# UWB-IP-Hardware.net
KiCad netlist of a schematic drawn in Altium Designer
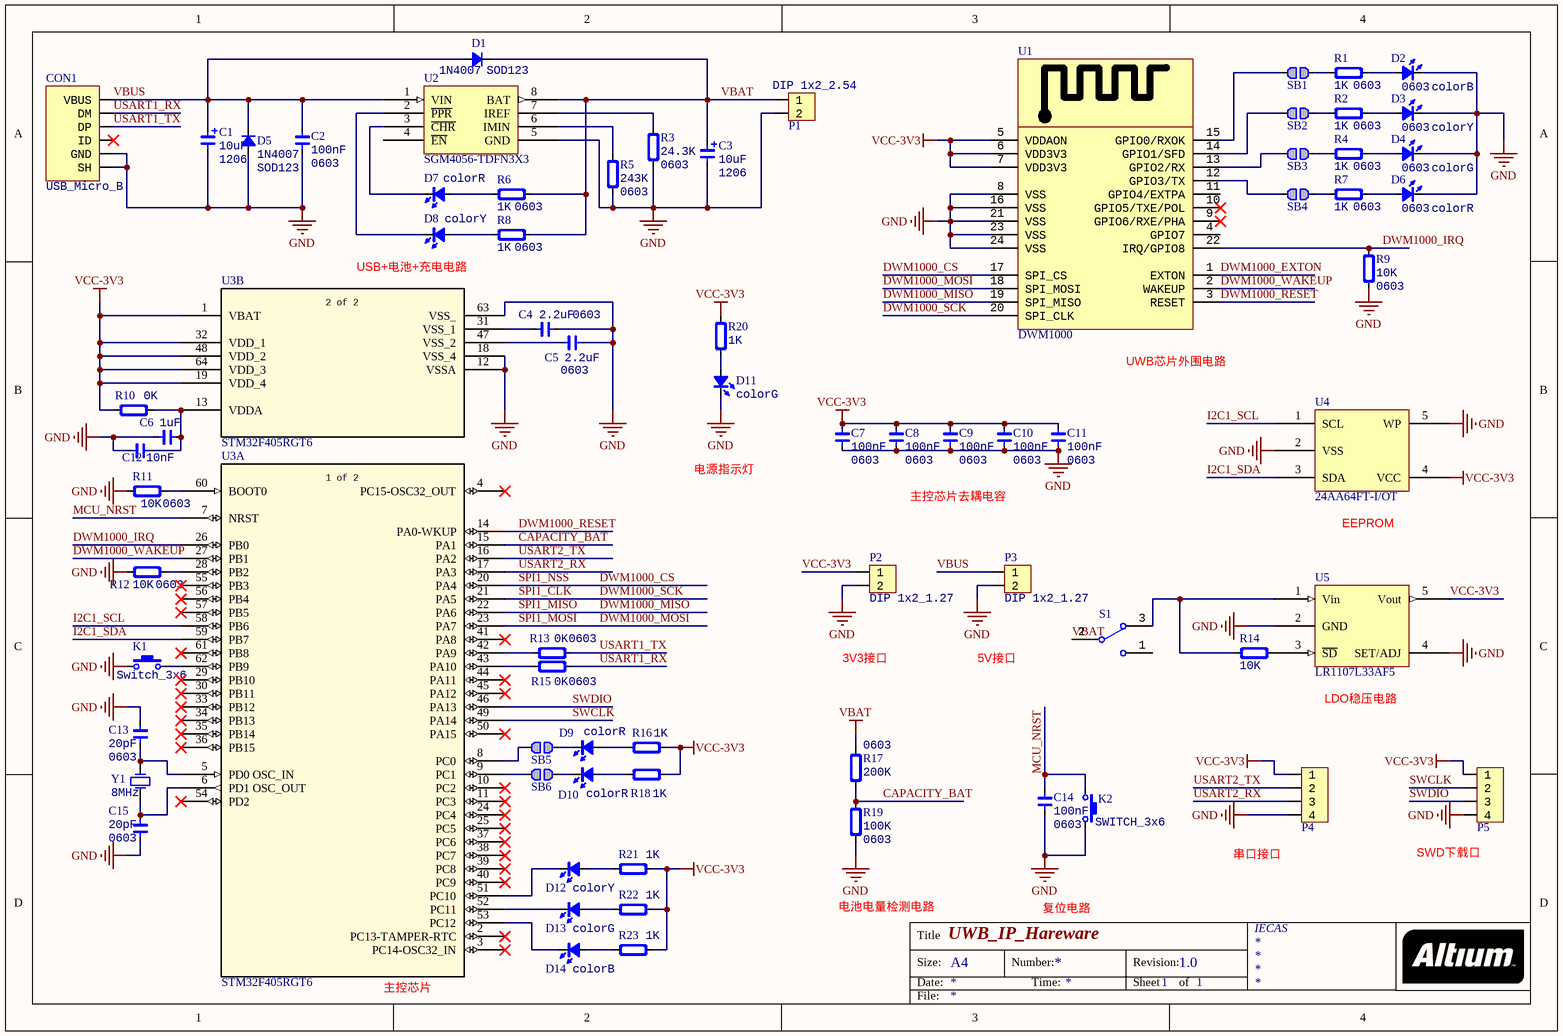
[diagram p0: UWB-IP-Hardware.SchDoc]

(export (version "E")
  (design (tool "Eeschema 10.0.6"))
  (components
    (comp (ref "C1")
      (value "10uF")
      (footprint "PCB_PassiveCap:CAP_TAN_A1206")
      (description "Capacitor Tantalum")
      (fields (field (name "TYPE") "1206"))
      (libsource (lib "SCH_Passive") (part "Cap_Tan_1206"))
    )
    (comp (ref "C2")
      (value "100nF")
      (footprint "PCB_PassiveCap:CAP_0603")
      (description "Capacitor")
      (fields (field (name "TYPE") "0603"))
      (libsource (lib "SCH_Passive") (part "Cap_0603"))
    )
    (comp (ref "C3")
      (value "10uF")
      (footprint "PCB_PassiveCap:CAP_TAN_A1206")
      (description "Capacitor Tantalum")
      (fields (field (name "TYPE") "1206"))
      (libsource (lib "SCH_Passive") (part "Cap_Tan_1206"))
    )
    (comp (ref "C4")
      (value "2.2uF")
      (footprint "PCB_PassiveCap:CAP_0603")
      (description "Capacitor")
      (fields (field (name "TYPE") "0603"))
      (libsource (lib "") (part "Cap_0603_1"))
    )
    (comp (ref "C5")
      (value "2.2uF")
      (footprint "PCB_PassiveCap:CAP_0603")
      (description "Capacitor")
      (fields (field (name "TYPE") "0603"))
      (libsource (lib "") (part "Cap_0603_1"))
    )
    (comp (ref "C6")
      (value "1uF")
      (footprint "PCB_PassiveCap:CAP_0603")
      (description "Capacitor")
      (libsource (lib "") (part "Cap_0603_2"))
    )
    (comp (ref "C7")
      (value "100nF")
      (footprint "PCB_PassiveCap:CAP_0603")
      (description "Capacitor")
      (fields (field (name "TYPE") "0603"))
      (libsource (lib "SCH_Passive") (part "Cap_0603"))
    )
    (comp (ref "C8")
      (value "100nF")
      (footprint "PCB_PassiveCap:CAP_0603")
      (description "Capacitor")
      (fields (field (name "TYPE") "0603"))
      (libsource (lib "SCH_Passive") (part "Cap_0603"))
    )
    (comp (ref "C9")
      (value "100nF")
      (footprint "PCB_PassiveCap:CAP_0603")
      (description "Capacitor")
      (fields (field (name "TYPE") "0603"))
      (libsource (lib "SCH_Passive") (part "Cap_0603"))
    )
    (comp (ref "C10")
      (value "100nF")
      (footprint "PCB_PassiveCap:CAP_0603")
      (description "Capacitor")
      (fields (field (name "TYPE") "0603"))
      (libsource (lib "SCH_Passive") (part "Cap_0603"))
    )
    (comp (ref "C11")
      (value "100nF")
      (footprint "PCB_PassiveCap:CAP_0603")
      (description "Capacitor")
      (fields (field (name "TYPE") "0603"))
      (libsource (lib "SCH_Passive") (part "Cap_0603"))
    )
    (comp (ref "C12")
      (value "10nF")
      (footprint "PCB_PassiveCap:CAP_0603")
      (description "Capacitor")
      (libsource (lib "") (part "Cap_0603_2"))
    )
    (comp (ref "C13")
      (value "20pF")
      (footprint "PCB_PassiveCap:CAP_0603")
      (description "Capacitor")
      (fields (field (name "TYPE") "0603"))
      (libsource (lib "SCH_Passive") (part "Cap_0603"))
    )
    (comp (ref "C14")
      (value "100nF")
      (footprint "PCB_PassiveCap:CAP_0603")
      (description "Capacitor")
      (fields (field (name "TYPE") "0603"))
      (libsource (lib "SCH_Passive") (part "Cap_0603"))
    )
    (comp (ref "C15")
      (value "20pF")
      (footprint "PCB_PassiveCap:CAP_0603")
      (description "Capacitor")
      (fields (field (name "TYPE") "0603"))
      (libsource (lib "SCH_Passive") (part "Cap_0603"))
    )
    (comp (ref "CON1")
      (value "USB_Micro_B")
      (footprint "PCB_USB:USB_Micro-AB")
      (description "USB")
      (libsource (lib "SCH_USB") (part "USB_Micro"))
    )
    (comp (ref "D1")
      (value "1N4007")
      (footprint "PCB_ActiveDIO:SOD-123")
      (description "Diode")
      (fields (field (name "TYPE") "SOD123"))
      (libsource (lib "SCH_Active") (part "Diode_SOD123"))
    )
    (comp (ref "D2")
      (value "colorB")
      (footprint "PCB_ActiveLED:LED_0603_BLUE")
      (description "LED")
      (fields (field (name "TYPE") "0603"))
      (libsource (lib "") (part "LED_0603_1"))
    )
    (comp (ref "D3")
      (value "colorY")
      (footprint "PCB_ActiveLED:LED_0603_YELLOW")
      (description "LED")
      (fields (field (name "TYPE") "0603"))
      (libsource (lib "") (part "LED_0603_1"))
    )
    (comp (ref "D4")
      (value "colorG")
      (footprint "PCB_ActiveLED:LED_0603_GREEN")
      (description "LED")
      (fields (field (name "TYPE") "0603"))
      (libsource (lib "") (part "LED_0603_1"))
    )
    (comp (ref "D5")
      (value "1N4007")
      (footprint "PCB_ActiveDIO:SOD-123")
      (description "Diode")
      (fields (field (name "TYPE") "SOD123"))
      (libsource (lib "SCH_Active") (part "Diode_SOD123"))
    )
    (comp (ref "D6")
      (value "colorR")
      (footprint "PCB_ActiveLED:LED_0603_RED")
      (description "LED")
      (fields (field (name "TYPE") "0603"))
      (libsource (lib "") (part "LED_0603_1"))
    )
    (comp (ref "D7")
      (value "colorR")
      (footprint "PCB_ActiveLED:LED_0603_RED")
      (description "LED")
      (libsource (lib "SCH_Active") (part "LED_0603"))
    )
    (comp (ref "D8")
      (value "colorY")
      (footprint "PCB_ActiveLED:LED_0603_YELLOW")
      (description "LED")
      (libsource (lib "SCH_Active") (part "LED_0603"))
    )
    (comp (ref "D9")
      (value "colorR")
      (footprint "PCB_ActiveLED:LED_0603_RED")
      (description "LED")
      (libsource (lib "SCH_Active") (part "LED_0603"))
    )
    (comp (ref "D10")
      (value "colorR")
      (footprint "PCB_ActiveLED:LED_0603_BLUE")
      (description "LED")
      (libsource (lib "SCH_Active") (part "LED_0603"))
    )
    (comp (ref "D11")
      (value "colorG")
      (footprint "PCB_ActiveLED:LED_0603_GREEN")
      (description "LED")
      (libsource (lib "") (part "LED_0603_2"))
    )
    (comp (ref "D12")
      (value "colorY")
      (footprint "PCB_ActiveLED:LED_0603_YELLOW")
      (description "LED")
      (libsource (lib "SCH_Active") (part "LED_0603"))
    )
    (comp (ref "D13")
      (value "colorG")
      (footprint "PCB_ActiveLED:LED_0603_GREEN")
      (description "LED")
      (libsource (lib "SCH_Active") (part "LED_0603"))
    )
    (comp (ref "D14")
      (value "colorB")
      (footprint "PCB_ActiveLED:LED_0603_BLUE")
      (description "LED")
      (libsource (lib "SCH_Active") (part "LED_0603"))
    )
    (comp (ref "K1")
      (value "Switch_3x6")
      (footprint "PCB_Switch:ButtonTACT_3x6x2.5_180")
      (description "Button")
      (libsource (lib "SCH_Switch") (part "ButtonTACT_3x6x2.5_180"))
    )
    (comp (ref "K2")
      (value "SWITCH_3x6")
      (footprint "PCB_Switch:ButtonTACT_3x6x2.5_180")
      (description "Button")
      (libsource (lib "SCH_Switch") (part "ButtonTACT_3x6x2.5_180"))
    )
    (comp (ref "P1")
      (value "DIP 1x2_2.54")
      (footprint "PCB_ConnectorHDR:HDR1X2_2.54_180")
      (description "Header")
      (libsource (lib "SCH_ConnectorHDR") (part "HDR1x2_2.54"))
    )
    (comp (ref "P2")
      (value "DIP 1x2_1.27")
      (footprint "PCB_ConnectorHDR:HDR1X2_1.27_180")
      (description "Header")
      (libsource (lib "SCH_ConnectorHDR") (part "HDR1x2_1.27"))
    )
    (comp (ref "P3")
      (value "DIP 1x2_1.27")
      (footprint "PCB_ConnectorHDR:HDR1X2_1.27_180")
      (description "Header")
      (libsource (lib "SCH_ConnectorHDR") (part "HDR1x2_1.27"))
    )
    (comp (ref "P4")
      (value "HDR1x4_2.54")
      (footprint "PCB_ConnectorHDR:HDR1x4_2.54_180")
      (description "Header")
      (libsource (lib "SCH_ConnectorHDR") (part "HDR1x4_2.54"))
    )
    (comp (ref "P5")
      (value "HDR1x4_2.54")
      (footprint "PCB_ConnectorHDR:HDR1x4_2.54_180")
      (description "Header")
      (libsource (lib "SCH_ConnectorHDR") (part "HDR1x4_2.54"))
    )
    (comp (ref "R1")
      (value "1K")
      (footprint "PCB_PassiveRes:RES_0603")
      (description "Resistor")
      (fields (field (name "TYPE") "0603"))
      (libsource (lib "SCH_Passive") (part "Res_0603"))
    )
    (comp (ref "R2")
      (value "1K")
      (footprint "PCB_PassiveRes:RES_0603")
      (description "Resistor")
      (fields (field (name "TYPE") "0603"))
      (libsource (lib "SCH_Passive") (part "Res_0603"))
    )
    (comp (ref "R3")
      (value "24.3K")
      (footprint "PCB_PassiveRes:RES_0603")
      (description "Resistor")
      (fields (field (name "TYPE") "0603"))
      (libsource (lib "SCH_Passive") (part "Res_0603"))
    )
    (comp (ref "R4")
      (value "1K")
      (footprint "PCB_PassiveRes:RES_0603")
      (description "Resistor")
      (fields (field (name "TYPE") "0603"))
      (libsource (lib "SCH_Passive") (part "Res_0603"))
    )
    (comp (ref "R5")
      (value "243K")
      (footprint "PCB_PassiveRes:RES_0603")
      (description "Resistor")
      (fields (field (name "TYPE") "0603"))
      (libsource (lib "SCH_Passive") (part "Res_0603"))
    )
    (comp (ref "R6")
      (value "1K")
      (footprint "PCB_PassiveRes:RES_0603")
      (description "Resistor")
      (fields (field (name "TYPE") "0603"))
      (libsource (lib "SCH_Passive") (part "Res_0603"))
    )
    (comp (ref "R7")
      (value "1K")
      (footprint "PCB_PassiveRes:RES_0603")
      (description "Resistor")
      (fields (field (name "TYPE") "0603"))
      (libsource (lib "SCH_Passive") (part "Res_0603"))
    )
    (comp (ref "R8")
      (value "1K")
      (footprint "PCB_PassiveRes:RES_0603")
      (description "Resistor")
      (fields (field (name "TYPE") "0603"))
      (libsource (lib "SCH_Passive") (part "Res_0603"))
    )
    (comp (ref "R9")
      (value "10K")
      (footprint "PCB_PassiveRes:RES_0603")
      (description "Resistor")
      (fields (field (name "TYPE") "0603"))
      (libsource (lib "SCH_Passive") (part "Res_0603"))
    )
    (comp (ref "R10")
      (value "0K")
      (footprint "PCB_PassiveRes:RES_0603")
      (description "Resistor")
      (libsource (lib "SCH_Passive") (part "Res_0603"))
    )
    (comp (ref "R11")
      (value "10K")
      (footprint "PCB_PassiveRes:RES_0603")
      (description "Resistor")
      (fields (field (name "TYPE") "0603"))
      (libsource (lib "SCH_Passive") (part "Res_0603"))
    )
    (comp (ref "R12")
      (value "10K")
      (footprint "PCB_PassiveRes:RES_0603")
      (description "Resistor")
      (fields (field (name "TYPE") "0603"))
      (libsource (lib "SCH_Passive") (part "Res_0603"))
    )
    (comp (ref "R13")
      (value "0K")
      (footprint "PCB_PassiveRes:RES_0603")
      (description "Resistor")
      (fields (field (name "TYPE") "0603"))
      (libsource (lib "SCH_Passive") (part "Res_0603"))
    )
    (comp (ref "R14")
      (value "10K")
      (footprint "PCB_PassiveRes:RES_0603")
      (description "Resistor")
      (libsource (lib "SCH_Passive") (part "Res_0603"))
    )
    (comp (ref "R15")
      (value "0K")
      (footprint "PCB_PassiveRes:RES_0603")
      (description "Resistor")
      (fields (field (name "TYPE") "0603"))
      (libsource (lib "SCH_Passive") (part "Res_0603"))
    )
    (comp (ref "R16")
      (value "1K")
      (footprint "PCB_PassiveRes:RES_0603")
      (description "Resistor")
      (libsource (lib "SCH_Passive") (part "Res_0603"))
    )
    (comp (ref "R17")
      (value "200K")
      (footprint "PCB_PassiveRes:RES_0603")
      (description "Resistor")
      (fields (field (name "TYPE") "0603"))
      (libsource (lib "SCH_Passive") (part "Res_0603"))
    )
    (comp (ref "R18")
      (value "1K")
      (footprint "PCB_PassiveRes:RES_0603")
      (description "Resistor")
      (libsource (lib "SCH_Passive") (part "Res_0603"))
    )
    (comp (ref "R19")
      (value "100K")
      (footprint "PCB_PassiveRes:RES_0603")
      (description "Resistor")
      (fields (field (name "TYPE") "0603"))
      (libsource (lib "SCH_Passive") (part "Res_0603"))
    )
    (comp (ref "R20")
      (value "1K")
      (footprint "PCB_PassiveRes:RES_0603")
      (description "Resistor")
      (libsource (lib "SCH_Passive") (part "Res_0603"))
    )
    (comp (ref "R21")
      (value "1K")
      (footprint "PCB_PassiveRes:RES_0603")
      (description "Resistor")
      (libsource (lib "SCH_Passive") (part "Res_0603"))
    )
    (comp (ref "R22")
      (value "1K")
      (footprint "PCB_PassiveRes:RES_0603")
      (description "Resistor")
      (libsource (lib "SCH_Passive") (part "Res_0603"))
    )
    (comp (ref "R23")
      (value "1K")
      (footprint "PCB_PassiveRes:RES_0603")
      (description "Resistor")
      (libsource (lib "SCH_Passive") (part "Res_0603"))
    )
    (comp (ref "S1")
      (value "SPDT 3P")
      (footprint "PCB_Switch:SwitchSPDT_2.8X6.6_90")
      (description "Switch")
      (libsource (lib "SCH_Switch") (part "SwitchSPDT_2.8x6.6_90"))
    )
    (comp (ref "SB1")
      (value "Solderbridge")
      (footprint "PCB_Mechanical:Solderbridge")
      (libsource (lib "SCH_Mechanical") (part "Solderbridge"))
    )
    (comp (ref "SB2")
      (value "Solderbridge")
      (footprint "PCB_Mechanical:Solderbridge")
      (libsource (lib "SCH_Mechanical") (part "Solderbridge"))
    )
    (comp (ref "SB3")
      (value "Solderbridge")
      (footprint "PCB_Mechanical:Solderbridge")
      (libsource (lib "SCH_Mechanical") (part "Solderbridge"))
    )
    (comp (ref "SB4")
      (value "Solderbridge")
      (footprint "PCB_Mechanical:Solderbridge")
      (libsource (lib "SCH_Mechanical") (part "Solderbridge"))
    )
    (comp (ref "SB5")
      (value "Solderbridge")
      (footprint "PCB_Mechanical:Solderbridge")
      (libsource (lib "SCH_Mechanical") (part "Solderbridge"))
    )
    (comp (ref "SB6")
      (value "Solderbridge")
      (footprint "PCB_Mechanical:Solderbridge")
      (libsource (lib "SCH_Mechanical") (part "Solderbridge"))
    )
    (comp (ref "U1")
      (value "DWM1000")
      (footprint "PCB_Module:DWM1000")
      (description "Module")
      (fields (field (name "MANUFACTURER") "Decawave Limited"))
      (libsource (lib "SCH_Module") (part "DWM1000"))
    )
    (comp (ref "U2")
      (value "SGM4056-TDFN3X3")
      (footprint "SGM4056-TDFN3X3-8L")
      (libsource (lib "UWB-IP-Schlib") (part "SGM4056"))
    )
    (comp (ref "U3")
      (value "STM32F405RGT6")
      (footprint "STM32F405RGT6-LQFP-64-M")
      (description "No Description Available")
      (fields (field (name "COPYRIGHT") "Copyright (C) 2018 Accelerated Designs. All rights reserved"))
      (libsource (lib "UWB-IP-Schlib") (part "STM32F405RGT6"))
    )
    (comp (ref "U4")
      (value "24AA64FT-I/OT")
      (footprint "EEPROM_24AA64FT-I/OT")
      (libsource (lib "UWB-IP-Schlib") (part "eeprom_24AA64FT-I/OT"))
    )
    (comp (ref "U5")
      (value "LR1107L33AF5")
      (footprint "LR1107L33AF5")
      (libsource (lib "UWB-IP-Schlib") (part "LR1107/EL33AF5"))
    )
    (comp (ref "Y1")
      (value "8MHz")
      (footprint "PCB_Oscillator:XT_3225_2")
      (description "Crystal Oscillator")
      (libsource (lib "SCH_Oscillator") (part "XTAL_3225_2P"))
    )
  )
  (nets
    (net (code "1") (name "/CAPACITY_BAT") (class "Default")
      (node (ref "R17") (pin "1") (pinfunction "1_1") (pintype "passive"))
      (node (ref "R19") (pin "2") (pinfunction "2_2") (pintype "passive"))
      (node (ref "U3") (pin "15") (pinfunction "PA1_15") (pintype "bidirectional"))
    )
    (net (code "2") (name "/DWM1000_CS") (class "Default")
      (node (ref "U1") (pin "17") (pinfunction "SPI_CS_17") (pintype "passive"))
      (node (ref "U3") (pin "20") (pinfunction "PA4_20") (pintype "bidirectional"))
    )
    (net (code "3") (name "/DWM1000_EXTON") (class "Default")
      (node (ref "U1") (pin "1") (pinfunction "EXTON_1") (pintype "passive"))
    )
    (net (code "4") (name "/DWM1000_IRQ") (class "Default")
      (node (ref "R9") (pin "2") (pinfunction "2_2") (pintype "passive"))
      (node (ref "U1") (pin "22") (pinfunction "IRQ/GPIO8_22") (pintype "passive"))
      (node (ref "U3") (pin "26") (pinfunction "PB0_26") (pintype "bidirectional"))
    )
    (net (code "5") (name "/DWM1000_MISO") (class "Default")
      (node (ref "U1") (pin "19") (pinfunction "SPI_MISO_19") (pintype "passive"))
      (node (ref "U3") (pin "22") (pinfunction "PA6_22") (pintype "bidirectional"))
    )
    (net (code "6") (name "/DWM1000_MOSI") (class "Default")
      (node (ref "U1") (pin "18") (pinfunction "SPI_MOSI_18") (pintype "passive"))
      (node (ref "U3") (pin "23") (pinfunction "PA7_23") (pintype "bidirectional"))
    )
    (net (code "7") (name "/DWM1000_RESET") (class "Default")
      (node (ref "U1") (pin "3") (pinfunction "RESET_3") (pintype "passive"))
      (node (ref "U3") (pin "14") (pinfunction "PA0-WKUP_14") (pintype "bidirectional"))
    )
    (net (code "8") (name "/DWM1000_SCK") (class "Default")
      (node (ref "U1") (pin "20") (pinfunction "SPI_CLK_20") (pintype "passive"))
      (node (ref "U3") (pin "21") (pinfunction "PA5_21") (pintype "bidirectional"))
    )
    (net (code "9") (name "/DWM1000_WAKEUP") (class "Default")
      (node (ref "U1") (pin "2") (pinfunction "WAKEUP_2") (pintype "passive"))
      (node (ref "U3") (pin "27") (pinfunction "PB1_27") (pintype "bidirectional"))
    )
    (net (code "10") (name "/I2C1_SCL") (class "Default")
      (node (ref "U3") (pin "58") (pinfunction "PB6_58") (pintype "bidirectional"))
      (node (ref "U4") (pin "1") (pinfunction "SCL_1") (pintype "passive"))
    )
    (net (code "11") (name "/I2C1_SDA") (class "Default")
      (node (ref "U3") (pin "59") (pinfunction "PB7_59") (pintype "bidirectional"))
      (node (ref "U4") (pin "3") (pinfunction "SDA_3") (pintype "passive"))
    )
    (net (code "12") (name "/MCU_NRST") (class "Default")
      (node (ref "C14") (pin "2") (pinfunction "2_2") (pintype "passive"))
      (node (ref "K2") (pin "1") (pinfunction "1_1") (pintype "passive"))
      (node (ref "U3") (pin "7") (pinfunction "NRST_7") (pintype "bidirectional"))
    )
    (net (code "13") (name "/SWCLK") (class "Default")
      (node (ref "P5") (pin "2") (pinfunction "2_2") (pintype "passive"))
      (node (ref "U3") (pin "49") (pinfunction "PA14_49") (pintype "bidirectional"))
    )
    (net (code "14") (name "/SWDIO") (class "Default")
      (node (ref "P5") (pin "3") (pinfunction "3_3") (pintype "passive"))
      (node (ref "U3") (pin "46") (pinfunction "PA13_46") (pintype "bidirectional"))
    )
    (net (code "15") (name "/USART1_RX") (class "Default")
      (node (ref "CON1") (pin "2") (pinfunction "DM_2") (pintype "passive"))
      (node (ref "R15") (pin "2") (pinfunction "2_2") (pintype "passive"))
    )
    (net (code "16") (name "/USART1_TX") (class "Default")
      (node (ref "CON1") (pin "3") (pinfunction "DP_3") (pintype "passive"))
      (node (ref "R13") (pin "2") (pinfunction "2_2") (pintype "passive"))
    )
    (net (code "17") (name "/USART2_RX") (class "Default")
      (node (ref "P4") (pin "3") (pinfunction "3_3") (pintype "passive"))
      (node (ref "U3") (pin "17") (pinfunction "PA3_17") (pintype "bidirectional"))
    )
    (net (code "18") (name "/USART2_TX") (class "Default")
      (node (ref "P4") (pin "2") (pinfunction "2_2") (pintype "passive"))
      (node (ref "U3") (pin "16") (pinfunction "PA2_16") (pintype "bidirectional"))
    )
    (net (code "19") (name "/VBUS") (class "Default")
      (node (ref "C1") (pin "1") (pinfunction "1_1") (pintype "passive"))
      (node (ref "C2") (pin "2") (pinfunction "2_2") (pintype "passive"))
      (node (ref "CON1") (pin "1") (pinfunction "VBUS_1") (pintype "passive"))
      (node (ref "D1") (pin "1") (pinfunction "A_1") (pintype "passive"))
      (node (ref "D5") (pin "2") (pinfunction "K_2") (pintype "passive"))
      (node (ref "P3") (pin "1") (pinfunction "1_1") (pintype "passive"))
      (node (ref "U2") (pin "1") (pinfunction "VIN_1") (pintype "input"))
    )
    (net (code "20") (name "GND") (class "Default")
      (node (ref "C1") (pin "2") (pinfunction "2_2") (pintype "passive"))
      (node (ref "C10") (pin "1") (pinfunction "1_1") (pintype "passive"))
      (node (ref "C11") (pin "1") (pinfunction "1_1") (pintype "passive"))
      (node (ref "C12") (pin "1") (pinfunction "1_1") (pintype "passive"))
      (node (ref "C13") (pin "2") (pinfunction "2_2") (pintype "passive"))
      (node (ref "C14") (pin "1") (pinfunction "1_1") (pintype "passive"))
      (node (ref "C15") (pin "1") (pinfunction "1_1") (pintype "passive"))
      (node (ref "C2") (pin "1") (pinfunction "1_1") (pintype "passive"))
      (node (ref "C3") (pin "2") (pinfunction "2_2") (pintype "passive"))
      (node (ref "C4") (pin "1") (pinfunction "1_1") (pintype "passive"))
      (node (ref "C5") (pin "1") (pinfunction "1_1") (pintype "passive"))
      (node (ref "C6") (pin "1") (pinfunction "1_1") (pintype "passive"))
      (node (ref "C7") (pin "1") (pinfunction "1_1") (pintype "passive"))
      (node (ref "C8") (pin "1") (pinfunction "1_1") (pintype "passive"))
      (node (ref "C9") (pin "1") (pinfunction "1_1") (pintype "passive"))
      (node (ref "CON1") (pin "0") (pinfunction "SH_0") (pintype "passive"))
      (node (ref "CON1") (pin "5") (pinfunction "GND_5") (pintype "passive"))
      (node (ref "D11") (pin "2") (pinfunction "K_2") (pintype "passive"))
      (node (ref "D2") (pin "2") (pinfunction "K_2") (pintype "passive"))
      (node (ref "D3") (pin "2") (pinfunction "K_2") (pintype "passive"))
      (node (ref "D4") (pin "2") (pinfunction "K_2") (pintype "passive"))
      (node (ref "D5") (pin "1") (pinfunction "A_1") (pintype "passive"))
      (node (ref "D6") (pin "2") (pinfunction "K_2") (pintype "passive"))
      (node (ref "K1") (pin "1") (pinfunction "1_1") (pintype "passive"))
      (node (ref "K2") (pin "2") (pinfunction "2_2") (pintype "passive"))
      (node (ref "P1") (pin "2") (pinfunction "2_2") (pintype "passive"))
      (node (ref "P2") (pin "2") (pinfunction "2_2") (pintype "passive"))
      (node (ref "P3") (pin "2") (pinfunction "2_2") (pintype "passive"))
      (node (ref "P4") (pin "4") (pinfunction "4_4") (pintype "passive"))
      (node (ref "P5") (pin "4") (pinfunction "4_4") (pintype "passive"))
      (node (ref "R11") (pin "1") (pinfunction "1_1") (pintype "passive"))
      (node (ref "R12") (pin "1") (pinfunction "1_1") (pintype "passive"))
      (node (ref "R19") (pin "1") (pinfunction "1_1") (pintype "passive"))
      (node (ref "R3") (pin "1") (pinfunction "1_1") (pintype "passive"))
      (node (ref "R5") (pin "1") (pinfunction "1_1") (pintype "passive"))
      (node (ref "R9") (pin "1") (pinfunction "1_1") (pintype "passive"))
      (node (ref "U1") (pin "16") (pinfunction "VSS_16") (pintype "passive"))
      (node (ref "U1") (pin "21") (pinfunction "VSS_21") (pintype "passive"))
      (node (ref "U1") (pin "23") (pinfunction "VSS_23") (pintype "passive"))
      (node (ref "U1") (pin "24") (pinfunction "VSS_24") (pintype "passive"))
      (node (ref "U1") (pin "8") (pinfunction "VSS_8") (pintype "passive"))
      (node (ref "U2") (pin "5") (pinfunction "GND_5") (pintype "passive"))
      (node (ref "U3") (pin "12") (pinfunction "VSSA_12") (pintype "power_in"))
      (node (ref "U3") (pin "18") (pinfunction "VSS_4_18") (pintype "power_in"))
      (node (ref "U3") (pin "63") (pinfunction "VSS__63") (pintype "power_in"))
      (node (ref "U4") (pin "2") (pinfunction "VSS_2") (pintype "power_in"))
      (node (ref "U4") (pin "5") (pinfunction "WP_5") (pintype "passive"))
      (node (ref "U5") (pin "2") (pinfunction "GND_2") (pintype "power_in"))
      (node (ref "U5") (pin "4") (pinfunction "SET/ADJ_4") (pintype "passive"))
    )
    (net (code "21") (name "Net-(D2-A)") (class "Default")
      (node (ref "D2") (pin "1") (pinfunction "A_1") (pintype "passive"))
      (node (ref "R1") (pin "2") (pinfunction "2_2") (pintype "passive"))
    )
    (net (code "22") (name "Net-(D3-A)") (class "Default")
      (node (ref "D3") (pin "1") (pinfunction "A_1") (pintype "passive"))
      (node (ref "R2") (pin "2") (pinfunction "2_2") (pintype "passive"))
    )
    (net (code "23") (name "Net-(D4-A)") (class "Default")
      (node (ref "D4") (pin "1") (pinfunction "A_1") (pintype "passive"))
      (node (ref "R4") (pin "2") (pinfunction "2_2") (pintype "passive"))
    )
    (net (code "24") (name "Net-(D6-A)") (class "Default")
      (node (ref "D6") (pin "1") (pinfunction "A_1") (pintype "passive"))
      (node (ref "R7") (pin "2") (pinfunction "2_2") (pintype "passive"))
    )
    (net (code "25") (name "Net-(D7-A)") (class "Default")
      (node (ref "D7") (pin "1") (pinfunction "A_1") (pintype "passive"))
      (node (ref "R6") (pin "1") (pinfunction "1_1") (pintype "passive"))
    )
    (net (code "26") (name "Net-(D7-K)") (class "Default")
      (node (ref "D7") (pin "2") (pinfunction "K_2") (pintype "passive"))
      (node (ref "U2") (pin "3") (pinfunction "~{CHR}_3") (pintype "passive"))
    )
    (net (code "27") (name "Net-(D8-A)") (class "Default")
      (node (ref "D8") (pin "1") (pinfunction "A_1") (pintype "passive"))
      (node (ref "R8") (pin "1") (pinfunction "1_1") (pintype "passive"))
    )
    (net (code "28") (name "Net-(D8-K)") (class "Default")
      (node (ref "D8") (pin "2") (pinfunction "K_2") (pintype "passive"))
      (node (ref "U2") (pin "2") (pinfunction "~{PPR}_2") (pintype "passive"))
    )
    (net (code "29") (name "Net-(D9-A)") (class "Default")
      (node (ref "D9") (pin "1") (pinfunction "A_1") (pintype "passive"))
      (node (ref "R16") (pin "1") (pinfunction "1_1") (pintype "passive"))
    )
    (net (code "30") (name "Net-(D9-K)") (class "Default")
      (node (ref "D9") (pin "2") (pinfunction "K_2") (pintype "passive"))
      (node (ref "SB5") (pin "2") (pinfunction "2_2") (pintype "passive"))
    )
    (net (code "31") (name "Net-(D10-A)") (class "Default")
      (node (ref "D10") (pin "1") (pinfunction "A_1") (pintype "passive"))
      (node (ref "R18") (pin "1") (pinfunction "1_1") (pintype "passive"))
    )
    (net (code "32") (name "Net-(D10-K)") (class "Default")
      (node (ref "D10") (pin "2") (pinfunction "K_2") (pintype "passive"))
      (node (ref "SB6") (pin "2") (pinfunction "2_2") (pintype "passive"))
    )
    (net (code "33") (name "Net-(D11-A)") (class "Default")
      (node (ref "D11") (pin "1") (pinfunction "A_1") (pintype "passive"))
      (node (ref "R20") (pin "2") (pinfunction "2_2") (pintype "passive"))
    )
    (net (code "34") (name "Net-(D12-A)") (class "Default")
      (node (ref "D12") (pin "1") (pinfunction "A_1") (pintype "passive"))
      (node (ref "R21") (pin "1") (pinfunction "1_1") (pintype "passive"))
    )
    (net (code "35") (name "Net-(D12-K)") (class "Default")
      (node (ref "D12") (pin "2") (pinfunction "K_2") (pintype "passive"))
      (node (ref "U3") (pin "51") (pinfunction "PC10_51") (pintype "bidirectional"))
    )
    (net (code "36") (name "Net-(D13-A)") (class "Default")
      (node (ref "D13") (pin "1") (pinfunction "A_1") (pintype "passive"))
      (node (ref "R22") (pin "1") (pinfunction "1_1") (pintype "passive"))
    )
    (net (code "37") (name "Net-(D13-K)") (class "Default")
      (node (ref "D13") (pin "2") (pinfunction "K_2") (pintype "passive"))
      (node (ref "U3") (pin "52") (pinfunction "PC11_52") (pintype "bidirectional"))
    )
    (net (code "38") (name "Net-(D14-A)") (class "Default")
      (node (ref "D14") (pin "1") (pinfunction "A_1") (pintype "passive"))
      (node (ref "R23") (pin "1") (pinfunction "1_1") (pintype "passive"))
    )
    (net (code "39") (name "Net-(D14-K)") (class "Default")
      (node (ref "D14") (pin "2") (pinfunction "K_2") (pintype "passive"))
      (node (ref "U3") (pin "53") (pinfunction "PC12_53") (pintype "bidirectional"))
    )
    (net (code "40") (name "Net-(R1-Pad1)") (class "Default")
      (node (ref "R1") (pin "1") (pinfunction "1_1") (pintype "passive"))
      (node (ref "SB1") (pin "2") (pinfunction "2_2") (pintype "passive"))
    )
    (net (code "41") (name "Net-(R2-Pad1)") (class "Default")
      (node (ref "R2") (pin "1") (pinfunction "1_1") (pintype "passive"))
      (node (ref "SB2") (pin "2") (pinfunction "2_2") (pintype "passive"))
    )
    (net (code "42") (name "Net-(R4-Pad1)") (class "Default")
      (node (ref "R4") (pin "1") (pinfunction "1_1") (pintype "passive"))
      (node (ref "SB3") (pin "2") (pinfunction "2_2") (pintype "passive"))
    )
    (net (code "43") (name "Net-(R7-Pad1)") (class "Default")
      (node (ref "R7") (pin "1") (pinfunction "1_1") (pintype "passive"))
      (node (ref "SB4") (pin "2") (pinfunction "2_2") (pintype "passive"))
    )
    (net (code "44") (name "Net-(U1-GPIO0{slash}RXOK)") (class "Default")
      (node (ref "SB1") (pin "1") (pinfunction "1_1") (pintype "passive"))
      (node (ref "U1") (pin "15") (pinfunction "GPIO0/RXOK_15") (pintype "passive"))
    )
    (net (code "45") (name "Net-(U1-GPIO1{slash}SFD)") (class "Default")
      (node (ref "SB2") (pin "1") (pinfunction "1_1") (pintype "passive"))
      (node (ref "U1") (pin "14") (pinfunction "GPIO1/SFD_14") (pintype "passive"))
    )
    (net (code "46") (name "Net-(U1-GPIO2{slash}RX)") (class "Default")
      (node (ref "SB3") (pin "1") (pinfunction "1_1") (pintype "passive"))
      (node (ref "U1") (pin "13") (pinfunction "GPIO2/RX_13") (pintype "passive"))
    )
    (net (code "47") (name "Net-(U1-GPIO3{slash}TX)") (class "Default")
      (node (ref "SB4") (pin "1") (pinfunction "1_1") (pintype "passive"))
      (node (ref "U1") (pin "12") (pinfunction "GPIO3/TX_12") (pintype "passive"))
    )
    (net (code "48") (name "Net-(U2-IMIN)") (class "Default")
      (node (ref "R5") (pin "2") (pinfunction "2_2") (pintype "passive"))
      (node (ref "U2") (pin "6") (pinfunction "IMIN_6") (pintype "passive"))
    )
    (net (code "49") (name "Net-(U2-IREF)") (class "Default")
      (node (ref "R3") (pin "2") (pinfunction "2_2") (pintype "passive"))
      (node (ref "U2") (pin "7") (pinfunction "IREF_7") (pintype "passive"))
    )
    (net (code "50") (name "Net-(U3A-BOOT0)") (class "Default")
      (node (ref "R11") (pin "2") (pinfunction "2_2") (pintype "passive"))
      (node (ref "U3") (pin "60") (pinfunction "BOOT0_60") (pintype "input"))
    )
    (net (code "51") (name "Net-(U3A-PA9)") (class "Default")
      (node (ref "R13") (pin "1") (pinfunction "1_1") (pintype "passive"))
      (node (ref "U3") (pin "42") (pinfunction "PA9_42") (pintype "bidirectional"))
    )
    (net (code "52") (name "Net-(U3A-PA10)") (class "Default")
      (node (ref "R15") (pin "1") (pinfunction "1_1") (pintype "passive"))
      (node (ref "U3") (pin "43") (pinfunction "PA10_43") (pintype "bidirectional"))
    )
    (net (code "53") (name "Net-(U3A-PB2)") (class "Default")
      (node (ref "R12") (pin "2") (pinfunction "2_2") (pintype "passive"))
      (node (ref "U3") (pin "28") (pinfunction "PB2_28") (pintype "bidirectional"))
    )
    (net (code "54") (name "Net-(U3A-PB9)") (class "Default")
      (node (ref "K1") (pin "2") (pinfunction "2_2") (pintype "passive"))
      (node (ref "U3") (pin "62") (pinfunction "PB9_62") (pintype "bidirectional"))
    )
    (net (code "55") (name "Net-(U3A-PC0)") (class "Default")
      (node (ref "SB5") (pin "1") (pinfunction "1_1") (pintype "passive"))
      (node (ref "U3") (pin "8") (pinfunction "PC0_8") (pintype "bidirectional"))
    )
    (net (code "56") (name "Net-(U3A-PC1)") (class "Default")
      (node (ref "SB6") (pin "1") (pinfunction "1_1") (pintype "passive"))
      (node (ref "U3") (pin "9") (pinfunction "PC1_9") (pintype "bidirectional"))
    )
    (net (code "57") (name "Net-(U3A-PD0_OSC_IN)") (class "Default")
      (node (ref "C13") (pin "1") (pinfunction "1_1") (pintype "passive"))
      (node (ref "U3") (pin "5") (pinfunction "PD0_OSC_IN_5") (pintype "input"))
      (node (ref "Y1") (pin "2") (pinfunction "OSC2_2") (pintype "passive"))
    )
    (net (code "58") (name "Net-(U3A-PD1_OSC_OUT)") (class "Default")
      (node (ref "C15") (pin "2") (pinfunction "2_2") (pintype "passive"))
      (node (ref "U3") (pin "6") (pinfunction "PD1_OSC_OUT_6") (pintype "output"))
      (node (ref "Y1") (pin "1") (pinfunction "OSC1_1") (pintype "passive"))
    )
    (net (code "59") (name "Net-(U3B-VDDA)") (class "Default")
      (node (ref "C12") (pin "2") (pinfunction "2_2") (pintype "passive"))
      (node (ref "C6") (pin "2") (pinfunction "2_2") (pintype "passive"))
      (node (ref "R10") (pin "2") (pinfunction "2_2") (pintype "passive"))
      (node (ref "U3") (pin "13") (pinfunction "VDDA_13") (pintype "power_in"))
    )
    (net (code "60") (name "Net-(U3B-VSS_1)") (class "Default")
      (node (ref "C4") (pin "2") (pinfunction "2_2") (pintype "passive"))
      (node (ref "U3") (pin "31") (pinfunction "VSS_1_31") (pintype "power_in"))
    )
    (net (code "61") (name "Net-(U3B-VSS_2)") (class "Default")
      (node (ref "C5") (pin "2") (pinfunction "2_2") (pintype "passive"))
      (node (ref "U3") (pin "47") (pinfunction "VSS_2_47") (pintype "power_in"))
    )
    (net (code "62") (name "Net-(U5-Vin)") (class "Default")
      (node (ref "R14") (pin "1") (pinfunction "1_1") (pintype "passive"))
      (node (ref "S1") (pin "3") (pinfunction "3_3") (pintype "passive"))
      (node (ref "U5") (pin "1") (pinfunction "Vin_1") (pintype "input"))
    )
    (net (code "63") (name "Net-(U5-~{SD})") (class "Default")
      (node (ref "R14") (pin "2") (pinfunction "2_2") (pintype "passive"))
      (node (ref "U5") (pin "3") (pinfunction "~{SD}_3") (pintype "input"))
    )
    (net (code "64") (name "VBAT") (class "Default")
      (node (ref "C3") (pin "1") (pinfunction "1_1") (pintype "passive"))
      (node (ref "D1") (pin "2") (pinfunction "K_2") (pintype "passive"))
      (node (ref "P1") (pin "1") (pinfunction "1_1") (pintype "passive"))
      (node (ref "R17") (pin "2") (pinfunction "2_2") (pintype "passive"))
      (node (ref "R6") (pin "2") (pinfunction "2_2") (pintype "passive"))
      (node (ref "R8") (pin "2") (pinfunction "2_2") (pintype "passive"))
      (node (ref "S1") (pin "2") (pinfunction "2_2") (pintype "passive"))
      (node (ref "U2") (pin "8") (pinfunction "BAT_8") (pintype "output"))
    )
    (net (code "65") (name "VCC-3V3") (class "Default")
      (node (ref "C10") (pin "2") (pinfunction "2_2") (pintype "passive"))
      (node (ref "C11") (pin "2") (pinfunction "2_2") (pintype "passive"))
      (node (ref "C7") (pin "2") (pinfunction "2_2") (pintype "passive"))
      (node (ref "C8") (pin "2") (pinfunction "2_2") (pintype "passive"))
      (node (ref "C9") (pin "2") (pinfunction "2_2") (pintype "passive"))
      (node (ref "P2") (pin "1") (pinfunction "1_1") (pintype "passive"))
      (node (ref "P4") (pin "1") (pinfunction "1_1") (pintype "passive"))
      (node (ref "P5") (pin "1") (pinfunction "1_1") (pintype "passive"))
      (node (ref "R10") (pin "1") (pinfunction "1_1") (pintype "passive"))
      (node (ref "R16") (pin "2") (pinfunction "2_2") (pintype "passive"))
      (node (ref "R18") (pin "2") (pinfunction "2_2") (pintype "passive"))
      (node (ref "R20") (pin "1") (pinfunction "1_1") (pintype "passive"))
      (node (ref "R21") (pin "2") (pinfunction "2_2") (pintype "passive"))
      (node (ref "R22") (pin "2") (pinfunction "2_2") (pintype "passive"))
      (node (ref "R23") (pin "2") (pinfunction "2_2") (pintype "passive"))
      (node (ref "U1") (pin "5") (pinfunction "VDDAON_5") (pintype "passive"))
      (node (ref "U1") (pin "6") (pinfunction "VDD3V3_6") (pintype "passive"))
      (node (ref "U1") (pin "7") (pinfunction "VDD3V3_7") (pintype "passive"))
      (node (ref "U3") (pin "1") (pinfunction "VBAT_1") (pintype "power_in"))
      (node (ref "U3") (pin "19") (pinfunction "VDD_4_19") (pintype "power_in"))
      (node (ref "U3") (pin "32") (pinfunction "VDD_1_32") (pintype "power_in"))
      (node (ref "U3") (pin "48") (pinfunction "VDD_2_48") (pintype "power_in"))
      (node (ref "U3") (pin "64") (pinfunction "VDD_3_64") (pintype "power_in"))
      (node (ref "U4") (pin "4") (pinfunction "VCC_4") (pintype "power_in"))
      (node (ref "U5") (pin "5") (pinfunction "Vout_5") (pintype "output"))
    )
    (net (code "66") (name "unconnected-(CON1-ID-Pad4)") (class "Default")
      (node (ref "CON1") (pin "4") (pinfunction "ID_4") (pintype "passive+no_connect"))
    )
    (net (code "67") (name "unconnected-(S1-Pad1)") (class "Default")
      (node (ref "S1") (pin "1") (pinfunction "1_1") (pintype "passive"))
    )
    (net (code "68") (name "unconnected-(U1-GPIO4{slash}EXTPA-Pad11)") (class "Default")
      (node (ref "U1") (pin "11") (pinfunction "GPIO4/EXTPA_11") (pintype "passive"))
    )
    (net (code "69") (name "unconnected-(U1-GPIO5{slash}TXE{slash}POL-Pad10)") (class "Default")
      (node (ref "U1") (pin "10") (pinfunction "GPIO5/TXE/POL_10") (pintype "passive+no_connect"))
    )
    (net (code "70") (name "unconnected-(U1-GPIO6{slash}RXE{slash}PHA-Pad9)") (class "Default")
      (node (ref "U1") (pin "9") (pinfunction "GPIO6/RXE/PHA_9") (pintype "passive+no_connect"))
    )
    (net (code "71") (name "unconnected-(U1-GPIO7-Pad4)") (class "Default")
      (node (ref "U1") (pin "4") (pinfunction "GPIO7_4") (pintype "passive"))
    )
    (net (code "72") (name "unconnected-(U2-~{EN}-Pad4)") (class "Default")
      (node (ref "U2") (pin "4") (pinfunction "~{EN}_4") (pintype "passive"))
    )
    (net (code "73") (name "unconnected-(U3A-PA8-Pad41)") (class "Default")
      (node (ref "U3") (pin "41") (pinfunction "PA8_41") (pintype "bidirectional+no_connect"))
    )
    (net (code "74") (name "unconnected-(U3A-PA11-Pad44)") (class "Default")
      (node (ref "U3") (pin "44") (pinfunction "PA11_44") (pintype "bidirectional+no_connect"))
    )
    (net (code "75") (name "unconnected-(U3A-PA12-Pad45)") (class "Default")
      (node (ref "U3") (pin "45") (pinfunction "PA12_45") (pintype "bidirectional+no_connect"))
    )
    (net (code "76") (name "unconnected-(U3A-PA15-Pad50)") (class "Default")
      (node (ref "U3") (pin "50") (pinfunction "PA15_50") (pintype "bidirectional+no_connect"))
    )
    (net (code "77") (name "unconnected-(U3A-PB3-Pad55)") (class "Default")
      (node (ref "U3") (pin "55") (pinfunction "PB3_55") (pintype "bidirectional+no_connect"))
    )
    (net (code "78") (name "unconnected-(U3A-PB4-Pad56)") (class "Default")
      (node (ref "U3") (pin "56") (pinfunction "PB4_56") (pintype "bidirectional+no_connect"))
    )
    (net (code "79") (name "unconnected-(U3A-PB5-Pad57)") (class "Default")
      (node (ref "U3") (pin "57") (pinfunction "PB5_57") (pintype "bidirectional+no_connect"))
    )
    (net (code "80") (name "unconnected-(U3A-PB8-Pad61)") (class "Default")
      (node (ref "U3") (pin "61") (pinfunction "PB8_61") (pintype "bidirectional+no_connect"))
    )
    (net (code "81") (name "unconnected-(U3A-PB10-Pad29)") (class "Default")
      (node (ref "U3") (pin "29") (pinfunction "PB10_29") (pintype "bidirectional+no_connect"))
    )
    (net (code "82") (name "unconnected-(U3A-PB11-Pad30)") (class "Default")
      (node (ref "U3") (pin "30") (pinfunction "PB11_30") (pintype "bidirectional+no_connect"))
    )
    (net (code "83") (name "unconnected-(U3A-PB12-Pad33)") (class "Default")
      (node (ref "U3") (pin "33") (pinfunction "PB12_33") (pintype "bidirectional+no_connect"))
    )
    (net (code "84") (name "unconnected-(U3A-PB13-Pad34)") (class "Default")
      (node (ref "U3") (pin "34") (pinfunction "PB13_34") (pintype "bidirectional+no_connect"))
    )
    (net (code "85") (name "unconnected-(U3A-PB14-Pad35)") (class "Default")
      (node (ref "U3") (pin "35") (pinfunction "PB14_35") (pintype "bidirectional+no_connect"))
    )
    (net (code "86") (name "unconnected-(U3A-PB15-Pad36)") (class "Default")
      (node (ref "U3") (pin "36") (pinfunction "PB15_36") (pintype "bidirectional+no_connect"))
    )
    (net (code "87") (name "unconnected-(U3A-PC2-Pad10)") (class "Default")
      (node (ref "U3") (pin "10") (pinfunction "PC2_10") (pintype "bidirectional+no_connect"))
    )
    (net (code "88") (name "unconnected-(U3A-PC3-Pad11)") (class "Default")
      (node (ref "U3") (pin "11") (pinfunction "PC3_11") (pintype "bidirectional+no_connect"))
    )
    (net (code "89") (name "unconnected-(U3A-PC4-Pad24)") (class "Default")
      (node (ref "U3") (pin "24") (pinfunction "PC4_24") (pintype "bidirectional+no_connect"))
    )
    (net (code "90") (name "unconnected-(U3A-PC5-Pad25)") (class "Default")
      (node (ref "U3") (pin "25") (pinfunction "PC5_25") (pintype "bidirectional+no_connect"))
    )
    (net (code "91") (name "unconnected-(U3A-PC6-Pad37)") (class "Default")
      (node (ref "U3") (pin "37") (pinfunction "PC6_37") (pintype "bidirectional+no_connect"))
    )
    (net (code "92") (name "unconnected-(U3A-PC7-Pad38)") (class "Default")
      (node (ref "U3") (pin "38") (pinfunction "PC7_38") (pintype "bidirectional+no_connect"))
    )
    (net (code "93") (name "unconnected-(U3A-PC8-Pad39)") (class "Default")
      (node (ref "U3") (pin "39") (pinfunction "PC8_39") (pintype "bidirectional+no_connect"))
    )
    (net (code "94") (name "unconnected-(U3A-PC9-Pad40)") (class "Default")
      (node (ref "U3") (pin "40") (pinfunction "PC9_40") (pintype "bidirectional+no_connect"))
    )
    (net (code "95") (name "unconnected-(U3A-PC13-TAMPER-RTC-Pad2)") (class "Default")
      (node (ref "U3") (pin "2") (pinfunction "PC13-TAMPER-RTC_2") (pintype "bidirectional+no_connect"))
    )
    (net (code "96") (name "unconnected-(U3A-PC14-OSC32_IN-Pad3)") (class "Default")
      (node (ref "U3") (pin "3") (pinfunction "PC14-OSC32_IN_3") (pintype "bidirectional+no_connect"))
    )
    (net (code "97") (name "unconnected-(U3A-PC15-OSC32_OUT-Pad4)") (class "Default")
      (node (ref "U3") (pin "4") (pinfunction "PC15-OSC32_OUT_4") (pintype "bidirectional+no_connect"))
    )
    (net (code "98") (name "unconnected-(U3A-PD2-Pad54)") (class "Default")
      (node (ref "U3") (pin "54") (pinfunction "PD2_54") (pintype "bidirectional+no_connect"))
    )
  )
)
